# ConverterSch.net
KiCad netlist of a schematic drawn in Altium Designer
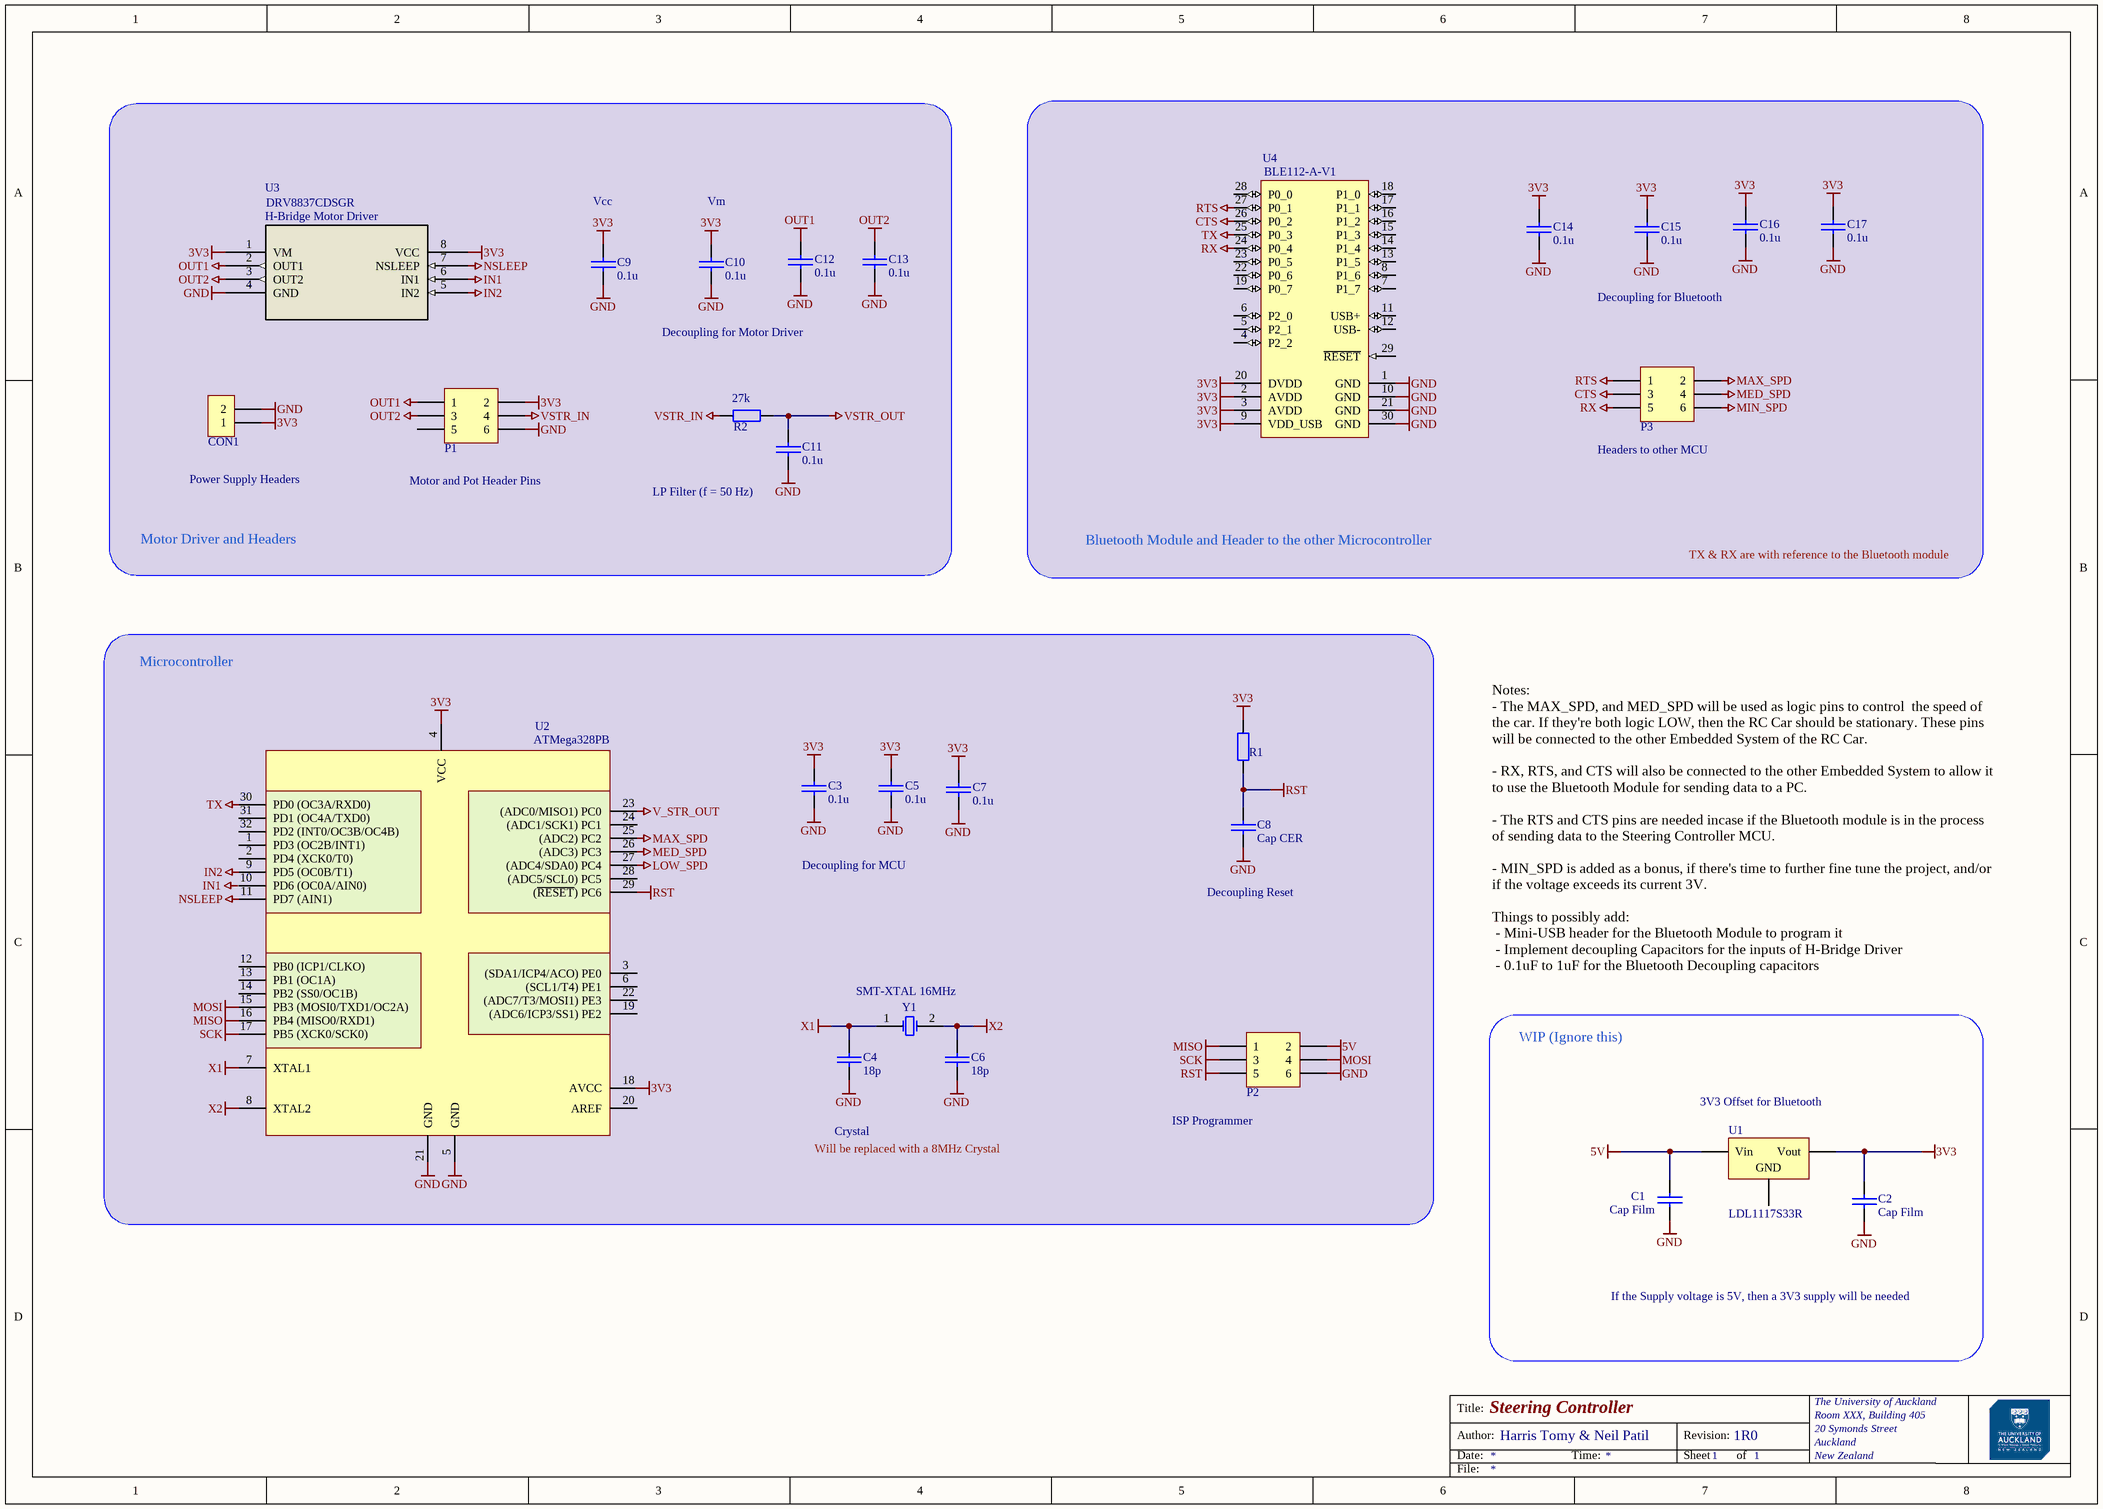
[diagram p0: ConverterSch.SchDoc]

(export (version "E")
  (design (tool "Eeschema 10.0.6"))
  (components
    (comp (ref "C1")
      (value "Cap Film")
      (footprint "LDECE4150KA0N00")
      (description "CAP FILM 1.5UF 10% 50VDC 2824")
      (fields (field (name "MPN") "LDECE4150KA0N00") (field (name "MANUFACTURER") "KEMET"))
      (libsource (lib "E209_Lib") (part "Cap Film SMD LDECE4150KA0N00"))
    )
    (comp (ref "C2")
      (value "Cap Film")
      (footprint "LDECE4150KA0N00")
      (description "CAP FILM 1.5UF 10% 50VDC 2824")
      (fields (field (name "MPN") "LDECE4150KA0N00") (field (name "MANUFACTURER") "KEMET"))
      (libsource (lib "E209_Lib") (part "Cap Film SMD LDECE4150KA0N00"))
    )
    (comp (ref "C3")
      (value "0.1u")
      (footprint "C1206")
      (description "CAP CER 0.1UF 100V C0G 1206")
      (fields (field (name "MPN") "C3216C0G2A104J160AC") (field (name "MANUFACTURER") "TDK Corporation"))
      (libsource (lib "E209_Lib") (part "Cap CER Decoup C3216C0G2A104J160AC"))
    )
    (comp (ref "C4")
      (value "18p")
      (footprint "C1206")
      (description "CAP CER 0.1UF 100V C0G 1206")
      (fields (field (name "MPN") "C3216C0G2A104J160AC") (field (name "MANUFACTURER") "TDK Corporation"))
      (libsource (lib "E209_Lib") (part "Cap CER Decoup C3216C0G2A104J160AC"))
    )
    (comp (ref "C5")
      (value "0.1u")
      (footprint "C1206")
      (description "CAP CER 0.1UF 100V C0G 1206")
      (fields (field (name "MPN") "C3216C0G2A104J160AC") (field (name "MANUFACTURER") "TDK Corporation"))
      (libsource (lib "E209_Lib") (part "Cap CER Decoup C3216C0G2A104J160AC"))
    )
    (comp (ref "C6")
      (value "18p")
      (footprint "C1206")
      (description "CAP CER 0.1UF 100V C0G 1206")
      (fields (field (name "MPN") "C3216C0G2A104J160AC") (field (name "MANUFACTURER") "TDK Corporation"))
      (libsource (lib "E209_Lib") (part "Cap CER Decoup C3216C0G2A104J160AC"))
    )
    (comp (ref "C7")
      (value "0.1u")
      (footprint "C1206")
      (description "CAP CER 0.1UF 100V C0G 1206")
      (fields (field (name "MPN") "C3216C0G2A104J160AC") (field (name "MANUFACTURER") "TDK Corporation"))
      (libsource (lib "E209_Lib") (part "Cap CER Decoup C3216C0G2A104J160AC"))
    )
    (comp (ref "C8")
      (value "Cap CER")
      (footprint "C1206")
      (description "CAP CER 0.1UF 100V C0G 1206")
      (fields (field (name "MPN") "C3216C0G2A104J160AC") (field (name "MANUFACTURER") "TDK Corporation"))
      (libsource (lib "E209_Lib") (part "Cap CER Decoup C3216C0G2A104J160AC"))
    )
    (comp (ref "C9")
      (value "0.1u")
      (footprint "C1206")
      (description "CAP CER 0.1UF 100V C0G 1206")
      (fields (field (name "MPN") "C3216C0G2A104J160AC") (field (name "MANUFACTURER") "TDK Corporation"))
      (libsource (lib "E209_Lib") (part "Cap CER Decoup C3216C0G2A104J160AC"))
    )
    (comp (ref "C10")
      (value "0.1u")
      (footprint "C1206")
      (description "CAP CER 0.1UF 100V C0G 1206")
      (fields (field (name "MPN") "C3216C0G2A104J160AC") (field (name "MANUFACTURER") "TDK Corporation"))
      (libsource (lib "E209_Lib") (part "Cap CER Decoup C3216C0G2A104J160AC"))
    )
    (comp (ref "C11")
      (value "0.1u")
      (footprint "C1206")
      (description "CAP CER 0.1UF 100V C0G 1206")
      (fields (field (name "MPN") "C3216C0G2A104J160AC") (field (name "MANUFACTURER") "TDK Corporation"))
      (libsource (lib "E209_Lib") (part "Cap CER Decoup C3216C0G2A104J160AC"))
    )
    (comp (ref "C12")
      (value "0.1u")
      (footprint "C1206")
      (description "CAP CER 0.1UF 100V C0G 1206")
      (fields (field (name "MPN") "C3216C0G2A104J160AC") (field (name "MANUFACTURER") "TDK Corporation"))
      (libsource (lib "E209_Lib") (part "Cap CER Decoup C3216C0G2A104J160AC"))
    )
    (comp (ref "C13")
      (value "0.1u")
      (footprint "C1206")
      (description "CAP CER 0.1UF 100V C0G 1206")
      (fields (field (name "MPN") "C3216C0G2A104J160AC") (field (name "MANUFACTURER") "TDK Corporation"))
      (libsource (lib "E209_Lib") (part "Cap CER Decoup C3216C0G2A104J160AC"))
    )
    (comp (ref "C14")
      (value "0.1u")
      (footprint "C1206")
      (description "CAP CER 0.1UF 100V C0G 1206")
      (fields (field (name "MPN") "C3216C0G2A104J160AC") (field (name "MANUFACTURER") "TDK Corporation"))
      (libsource (lib "E209_Lib") (part "Cap CER Decoup C3216C0G2A104J160AC"))
    )
    (comp (ref "C15")
      (value "0.1u")
      (footprint "C1206")
      (description "CAP CER 0.1UF 100V C0G 1206")
      (fields (field (name "MPN") "C3216C0G2A104J160AC") (field (name "MANUFACTURER") "TDK Corporation"))
      (libsource (lib "E209_Lib") (part "Cap CER Decoup C3216C0G2A104J160AC"))
    )
    (comp (ref "C16")
      (value "0.1u")
      (footprint "C1206")
      (description "CAP CER 0.1UF 100V C0G 1206")
      (fields (field (name "MPN") "C3216C0G2A104J160AC") (field (name "MANUFACTURER") "TDK Corporation"))
      (libsource (lib "E209_Lib") (part "Cap CER Decoup C3216C0G2A104J160AC"))
    )
    (comp (ref "C17")
      (value "0.1u")
      (footprint "C1206")
      (description "CAP CER 0.1UF 100V C0G 1206")
      (fields (field (name "MPN") "C3216C0G2A104J160AC") (field (name "MANUFACTURER") "TDK Corporation"))
      (libsource (lib "E209_Lib") (part "Cap CER Decoup C3216C0G2A104J160AC"))
    )
    (comp (ref "CON1")
      (value "Header 2X1")
      (footprint "HDR2X1_2P54")
      (libsource (lib "CommonDevices_V1") (part "HDR2X1"))
    )
    (comp (ref "P1")
      (value "HDR3X2")
      (footprint "HDR2X3_2P54")
      (description "Header, 3-Pin, Dual row")
      (libsource (lib "CommonDevices_V1") (part "HDR3X2"))
    )
    (comp (ref "P2")
      (value "HDR3X2")
      (footprint "HDR2X3_2P54")
      (description "Header, 3-Pin, Dual row")
      (libsource (lib "CommonDevices_V1") (part "HDR3X2"))
    )
    (comp (ref "P3")
      (value "HDR3X2")
      (footprint "HDR2X3_2P54")
      (description "Header, 3-Pin, Dual row")
      (libsource (lib "CommonDevices_V1") (part "HDR3X2"))
    )
    (comp (ref "R1")
      (value "Resistor 1206")
      (footprint "R1206")
      (description "RES1206")
      (fields (field (name "MPN") "?"))
      (libsource (lib "E209_Lib") (part "RES1206"))
    )
    (comp (ref "R2")
      (value "Resistor 0805")
      (footprint "R0805")
      (description "RES0805")
      (fields (field (name "MPN") "?"))
      (libsource (lib "E209_Lib") (part "RES0805"))
    )
    (comp (ref "U1")
      (value "LDL1117S33R")
      (footprint "SOT223L")
      (description "IC REG LINEAR 3.3V 1.2A SOT223")
      (fields (field (name "MANUFACTURER") "STMicroelectronics"))
      (libsource (lib "E209_Lib") (part "LDO LDL1117S33R"))
    )
    (comp (ref "U2")
      (value "ATMega328PB")
      (footprint "TQFP32")
      (description "IC MCU 8BIT 32KB FLASH 32TQFP")
      (libsource (lib "CommonDevices_V1") (part "ATMega328PB"))
    )
    (comp (ref "U3")
      (value "DRV8837CDSGR")
      (footprint "DSG8_P9X1P6_TEX")
      (description "No Description Available")
      (fields (field (name "COPYRIGHT") "Copyright (C) 2018 Accelerated Designs. All rights reserved"))
      (libsource (lib "H-Bridge_Driver_DRV8837C") (part "DRV8837CDSGR"))
    )
    (comp (ref "U4")
      (value "BLE112-A-V1")
      (footprint "BLUE-BLE112-A-V1_V")
      (libsource (lib "Integrated_Library1") (part "BLE112-A-V1"))
    )
    (comp (ref "Y1")
      (value "SMT-XTAL 16MHz")
      (footprint "HC49-US")
      (description "9C-16.000MAAJ-T crystal 16.0000MHZ 18PF SMD")
      (fields
        (field (name "MANUFACTURER") "TXC CORPORATION")
        (field (name "MANUFACTURER PART NUMBER") "9C-16.000MAAJ-T")
      )
      (libsource (lib "EE209_Library") (part "TXC9C-16_XTAL_SMT"))
    )
  )
  (nets
    (net (code "1") (name "3V3") (class "Default")
      (node (ref "C10") (pin "2") (pinfunction "2_2") (pintype "passive"))
      (node (ref "C14") (pin "2") (pinfunction "2_2") (pintype "passive"))
      (node (ref "C15") (pin "2") (pinfunction "2_2") (pintype "passive"))
      (node (ref "C16") (pin "2") (pinfunction "2_2") (pintype "passive"))
      (node (ref "C17") (pin "2") (pinfunction "2_2") (pintype "passive"))
      (node (ref "C2") (pin "2") (pinfunction "2_2") (pintype "passive"))
      (node (ref "C3") (pin "2") (pinfunction "2_2") (pintype "passive"))
      (node (ref "C5") (pin "2") (pinfunction "2_2") (pintype "passive"))
      (node (ref "C7") (pin "2") (pinfunction "2_2") (pintype "passive"))
      (node (ref "C9") (pin "2") (pinfunction "2_2") (pintype "passive"))
      (node (ref "CON1") (pin "1") (pinfunction "1_1") (pintype "passive"))
      (node (ref "P1") (pin "2") (pinfunction "2_2") (pintype "passive"))
      (node (ref "R1") (pin "1") (pinfunction "1_1") (pintype "passive"))
      (node (ref "U1") (pin "2") (pinfunction "Vout_2") (pintype "passive"))
      (node (ref "U2") (pin "4") (pinfunction "VCC_4") (pintype "passive"))
      (node (ref "U3") (pin "1") (pinfunction "VM_1") (pintype "power_in"))
      (node (ref "U3") (pin "8") (pinfunction "VCC_8") (pintype "power_in"))
      (node (ref "U4") (pin "2") (pinfunction "AVDD_2") (pintype "power_in"))
      (node (ref "U4") (pin "20") (pinfunction "DVDD_20") (pintype "power_in"))
      (node (ref "U4") (pin "3") (pinfunction "AVDD_3") (pintype "power_in"))
      (node (ref "U4") (pin "9") (pinfunction "VDD_USB_9") (pintype "power_in"))
    )
    (net (code "2") (name "5V") (class "Default")
      (node (ref "C1") (pin "2") (pinfunction "2_2") (pintype "passive"))
      (node (ref "P2") (pin "2") (pinfunction "2_2") (pintype "passive"))
      (node (ref "U1") (pin "3") (pinfunction "Vin_3") (pintype "passive"))
    )
    (net (code "3") (name "CTS") (class "Default")
      (node (ref "P3") (pin "3") (pinfunction "3_3") (pintype "passive"))
      (node (ref "U4") (pin "26") (pinfunction "P0_2_26") (pintype "bidirectional"))
    )
    (net (code "4") (name "GND") (class "Default")
      (node (ref "C1") (pin "1") (pinfunction "1_1") (pintype "passive"))
      (node (ref "C10") (pin "1") (pinfunction "1_1") (pintype "passive"))
      (node (ref "C11") (pin "1") (pinfunction "1_1") (pintype "passive"))
      (node (ref "C12") (pin "1") (pinfunction "1_1") (pintype "passive"))
      (node (ref "C13") (pin "1") (pinfunction "1_1") (pintype "passive"))
      (node (ref "C14") (pin "1") (pinfunction "1_1") (pintype "passive"))
      (node (ref "C15") (pin "1") (pinfunction "1_1") (pintype "passive"))
      (node (ref "C16") (pin "1") (pinfunction "1_1") (pintype "passive"))
      (node (ref "C17") (pin "1") (pinfunction "1_1") (pintype "passive"))
      (node (ref "C2") (pin "1") (pinfunction "1_1") (pintype "passive"))
      (node (ref "C3") (pin "1") (pinfunction "1_1") (pintype "passive"))
      (node (ref "C4") (pin "1") (pinfunction "1_1") (pintype "passive"))
      (node (ref "C5") (pin "1") (pinfunction "1_1") (pintype "passive"))
      (node (ref "C6") (pin "1") (pinfunction "1_1") (pintype "passive"))
      (node (ref "C7") (pin "1") (pinfunction "1_1") (pintype "passive"))
      (node (ref "C8") (pin "1") (pinfunction "1_1") (pintype "passive"))
      (node (ref "C9") (pin "1") (pinfunction "1_1") (pintype "passive"))
      (node (ref "CON1") (pin "2") (pinfunction "2_2") (pintype "passive"))
      (node (ref "P1") (pin "6") (pinfunction "6_6") (pintype "passive"))
      (node (ref "P2") (pin "6") (pinfunction "6_6") (pintype "passive"))
      (node (ref "U2") (pin "21") (pinfunction "GND_21") (pintype "passive"))
      (node (ref "U2") (pin "5") (pinfunction "GND_5") (pintype "passive"))
      (node (ref "U3") (pin "4") (pinfunction "GND_4") (pintype "power_in"))
      (node (ref "U4") (pin "1") (pinfunction "GND_1") (pintype "power_in"))
      (node (ref "U4") (pin "10") (pinfunction "GND_10") (pintype "power_in"))
      (node (ref "U4") (pin "21") (pinfunction "GND_21") (pintype "power_in"))
      (node (ref "U4") (pin "30") (pinfunction "GND_30") (pintype "power_in"))
    )
    (net (code "5") (name "IN1") (class "Default")
      (node (ref "U3") (pin "6") (pinfunction "IN1_6") (pintype "input"))
    )
    (net (code "6") (name "IN2") (class "Default")
      (node (ref "U2") (pin "9") (pinfunction "PD5_(OC0B/T1)_9") (pintype "passive"))
      (node (ref "U3") (pin "5") (pinfunction "IN2_5") (pintype "input"))
    )
    (net (code "7") (name "LOW_SPD") (class "Default")
      (node (ref "U2") (pin "27") (pinfunction "(ADC4/SDA0)_PC4_27") (pintype "passive"))
    )
    (net (code "8") (name "MAX_SPD") (class "Default")
      (node (ref "P3") (pin "2") (pinfunction "2_2") (pintype "passive"))
      (node (ref "U2") (pin "25") (pinfunction "(ADC2)_PC2_25") (pintype "passive"))
    )
    (net (code "9") (name "MED_SPD") (class "Default")
      (node (ref "P3") (pin "4") (pinfunction "4_4") (pintype "passive"))
      (node (ref "U2") (pin "26") (pinfunction "(ADC3)_PC3_26") (pintype "passive"))
    )
    (net (code "10") (name "MIN_SPD") (class "Default")
      (node (ref "P3") (pin "6") (pinfunction "6_6") (pintype "passive"))
    )
    (net (code "11") (name "MISO") (class "Default")
      (node (ref "P2") (pin "1") (pinfunction "1_1") (pintype "passive"))
      (node (ref "U2") (pin "16") (pinfunction "PB4_(MISO0/RXD1)_16") (pintype "passive"))
    )
    (net (code "12") (name "MOSI") (class "Default")
      (node (ref "P2") (pin "4") (pinfunction "4_4") (pintype "passive"))
      (node (ref "U2") (pin "15") (pinfunction "PB3_(MOSI0/TXD1/OC2A)_15") (pintype "passive"))
    )
    (net (code "13") (name "NSLEEP") (class "Default")
      (node (ref "U2") (pin "11") (pinfunction "PD7_(AIN1)_11") (pintype "passive"))
      (node (ref "U3") (pin "7") (pinfunction "NSLEEP_7") (pintype "input"))
    )
    (net (code "14") (name "OUT1") (class "Default")
      (node (ref "C12") (pin "2") (pinfunction "2_2") (pintype "passive"))
      (node (ref "P1") (pin "1") (pinfunction "1_1") (pintype "passive"))
      (node (ref "U3") (pin "2") (pinfunction "OUT1_2") (pintype "output"))
    )
    (net (code "15") (name "OUT2") (class "Default")
      (node (ref "C13") (pin "2") (pinfunction "2_2") (pintype "passive"))
      (node (ref "P1") (pin "3") (pinfunction "3_3") (pintype "passive"))
      (node (ref "U3") (pin "3") (pinfunction "OUT2_3") (pintype "output"))
    )
    (net (code "16") (name "RST") (class "Default")
      (node (ref "C8") (pin "2") (pinfunction "2_2") (pintype "passive"))
      (node (ref "P2") (pin "5") (pinfunction "5_5") (pintype "passive"))
      (node (ref "R1") (pin "2") (pinfunction "2_2") (pintype "passive"))
      (node (ref "U2") (pin "29") (pinfunction "(~{RESET})_PC6_29") (pintype "passive"))
    )
    (net (code "17") (name "RTS") (class "Default")
      (node (ref "P3") (pin "1") (pinfunction "1_1") (pintype "passive"))
      (node (ref "U4") (pin "27") (pinfunction "P0_1_27") (pintype "bidirectional"))
    )
    (net (code "18") (name "RX") (class "Default")
      (node (ref "P3") (pin "5") (pinfunction "5_5") (pintype "passive"))
      (node (ref "U4") (pin "24") (pinfunction "P0_4_24") (pintype "bidirectional"))
    )
    (net (code "19") (name "SCK") (class "Default")
      (node (ref "P2") (pin "3") (pinfunction "3_3") (pintype "passive"))
      (node (ref "U2") (pin "17") (pinfunction "PB5_(XCK0/SCK0)_17") (pintype "passive"))
    )
    (net (code "20") (name "TX") (class "Default")
      (node (ref "U2") (pin "30") (pinfunction "PD0_(OC3A/RXD0)_30") (pintype "passive"))
      (node (ref "U4") (pin "25") (pinfunction "P0_3_25") (pintype "bidirectional"))
    )
    (net (code "21") (name "VSTR_IN") (class "Default")
      (node (ref "P1") (pin "4") (pinfunction "4_4") (pintype "passive"))
      (node (ref "R2") (pin "1") (pinfunction "1_1") (pintype "passive"))
    )
    (net (code "22") (name "VSTR_OUT") (class "Default")
      (node (ref "C11") (pin "2") (pinfunction "2_2") (pintype "passive"))
      (node (ref "R2") (pin "2") (pinfunction "2_2") (pintype "passive"))
    )
    (net (code "23") (name "V_STR_OUT") (class "Default")
      (node (ref "U2") (pin "23") (pinfunction "(ADC0/MISO1)_PC0_23") (pintype "passive"))
    )
    (net (code "24") (name "X1") (class "Default")
      (node (ref "C4") (pin "2") (pinfunction "2_2") (pintype "passive"))
      (node (ref "U2") (pin "7") (pinfunction "XTAL1_7") (pintype "passive"))
      (node (ref "Y1") (pin "1") (pinfunction "OSC1_1") (pintype "passive"))
    )
    (net (code "25") (name "X2") (class "Default")
      (node (ref "C6") (pin "2") (pinfunction "2_2") (pintype "passive"))
      (node (ref "U2") (pin "8") (pinfunction "XTAL2_8") (pintype "passive"))
      (node (ref "Y1") (pin "2") (pinfunction "OSC2_2") (pintype "passive"))
    )
    (net (code "26") (name "unconnected-(P1-Pad5)") (class "Default")
      (node (ref "P1") (pin "5") (pinfunction "5_5") (pintype "passive"))
    )
    (net (code "27") (name "unconnected-(U1-GND-Pad1)") (class "Default")
      (node (ref "U1") (pin "1") (pinfunction "GND_1") (pintype "passive"))
    )
    (net (code "28") (name "unconnected-(U2-(ADC1{slash}SCK1)_PC1-Pad24)") (class "Default")
      (node (ref "U2") (pin "24") (pinfunction "(ADC1/SCK1)_PC1_24") (pintype "passive"))
    )
    (net (code "29") (name "unconnected-(U2-(ADC5{slash}SCL0)_PC5-Pad28)") (class "Default")
      (node (ref "U2") (pin "28") (pinfunction "(ADC5/SCL0)_PC5_28") (pintype "passive"))
    )
    (net (code "30") (name "unconnected-(U2-(ADC6{slash}ICP3{slash}SS1)_PE2-Pad19)") (class "Default")
      (node (ref "U2") (pin "19") (pinfunction "(ADC6/ICP3/SS1)_PE2_19") (pintype "passive"))
    )
    (net (code "31") (name "unconnected-(U2-(ADC7{slash}T3{slash}MOSI1)_PE3-Pad22)") (class "Default")
      (node (ref "U2") (pin "22") (pinfunction "(ADC7/T3/MOSI1)_PE3_22") (pintype "passive"))
    )
    (net (code "32") (name "unconnected-(U2-(SCL1{slash}T4)_PE1-Pad6)") (class "Default")
      (node (ref "U2") (pin "6") (pinfunction "(SCL1/T4)_PE1_6") (pintype "passive"))
    )
    (net (code "33") (name "unconnected-(U2-(SDA1{slash}ICP4{slash}ACO)_PE0-Pad3)") (class "Default")
      (node (ref "U2") (pin "3") (pinfunction "(SDA1/ICP4/ACO)_PE0_3") (pintype "passive"))
    )
    (net (code "34") (name "unconnected-(U2-AREF-Pad20)") (class "Default")
      (node (ref "U2") (pin "20") (pinfunction "AREF_20") (pintype "passive"))
    )
    (net (code "35") (name "unconnected-(U2-AVCC-Pad18)") (class "Default")
      (node (ref "U2") (pin "18") (pinfunction "AVCC_18") (pintype "passive"))
    )
    (net (code "36") (name "unconnected-(U2-PB0_(ICP1{slash}CLKO)-Pad12)") (class "Default")
      (node (ref "U2") (pin "12") (pinfunction "PB0_(ICP1/CLKO)_12") (pintype "passive"))
    )
    (net (code "37") (name "unconnected-(U2-PB1_(OC1A)-Pad13)") (class "Default")
      (node (ref "U2") (pin "13") (pinfunction "PB1_(OC1A)_13") (pintype "passive"))
    )
    (net (code "38") (name "unconnected-(U2-PB2_(SS0{slash}OC1B)-Pad14)") (class "Default")
      (node (ref "U2") (pin "14") (pinfunction "PB2_(SS0/OC1B)_14") (pintype "passive"))
    )
    (net (code "39") (name "unconnected-(U2-PD1_(OC4A{slash}TXD0)-Pad31)") (class "Default")
      (node (ref "U2") (pin "31") (pinfunction "PD1_(OC4A/TXD0)_31") (pintype "passive"))
    )
    (net (code "40") (name "unconnected-(U2-PD2_(INT0{slash}OC3B{slash}OC4B)-Pad32)") (class "Default")
      (node (ref "U2") (pin "32") (pinfunction "PD2_(INT0/OC3B/OC4B)_32") (pintype "passive"))
    )
    (net (code "41") (name "unconnected-(U2-PD3_(OC2B{slash}INT1)-Pad1)") (class "Default")
      (node (ref "U2") (pin "1") (pinfunction "PD3_(OC2B/INT1)_1") (pintype "passive"))
    )
    (net (code "42") (name "unconnected-(U2-PD4_(XCK0{slash}T0)-Pad2)") (class "Default")
      (node (ref "U2") (pin "2") (pinfunction "PD4_(XCK0/T0)_2") (pintype "passive"))
    )
    (net (code "43") (name "unconnected-(U2-PD6_(OC0A{slash}AIN0)-Pad10)") (class "Default")
      (node (ref "U2") (pin "10") (pinfunction "PD6_(OC0A/AIN0)_10") (pintype "passive"))
    )
    (net (code "44") (name "unconnected-(U4-P0_0-Pad28)") (class "Default")
      (node (ref "U4") (pin "28") (pinfunction "P0_0_28") (pintype "bidirectional"))
    )
    (net (code "45") (name "unconnected-(U4-P0_5-Pad23)") (class "Default")
      (node (ref "U4") (pin "23") (pinfunction "P0_5_23") (pintype "bidirectional"))
    )
    (net (code "46") (name "unconnected-(U4-P0_6-Pad22)") (class "Default")
      (node (ref "U4") (pin "22") (pinfunction "P0_6_22") (pintype "bidirectional"))
    )
    (net (code "47") (name "unconnected-(U4-P0_7-Pad19)") (class "Default")
      (node (ref "U4") (pin "19") (pinfunction "P0_7_19") (pintype "bidirectional"))
    )
    (net (code "48") (name "unconnected-(U4-P1_0-Pad18)") (class "Default")
      (node (ref "U4") (pin "18") (pinfunction "P1_0_18") (pintype "bidirectional"))
    )
    (net (code "49") (name "unconnected-(U4-P1_1-Pad17)") (class "Default")
      (node (ref "U4") (pin "17") (pinfunction "P1_1_17") (pintype "bidirectional"))
    )
    (net (code "50") (name "unconnected-(U4-P1_2-Pad16)") (class "Default")
      (node (ref "U4") (pin "16") (pinfunction "P1_2_16") (pintype "bidirectional"))
    )
    (net (code "51") (name "unconnected-(U4-P1_3-Pad15)") (class "Default")
      (node (ref "U4") (pin "15") (pinfunction "P1_3_15") (pintype "bidirectional"))
    )
    (net (code "52") (name "unconnected-(U4-P1_4-Pad14)") (class "Default")
      (node (ref "U4") (pin "14") (pinfunction "P1_4_14") (pintype "bidirectional"))
    )
    (net (code "53") (name "unconnected-(U4-P1_5-Pad13)") (class "Default")
      (node (ref "U4") (pin "13") (pinfunction "P1_5_13") (pintype "bidirectional"))
    )
    (net (code "54") (name "unconnected-(U4-P1_6-Pad8)") (class "Default")
      (node (ref "U4") (pin "8") (pinfunction "P1_6_8") (pintype "bidirectional"))
    )
    (net (code "55") (name "unconnected-(U4-P1_7-Pad7)") (class "Default")
      (node (ref "U4") (pin "7") (pinfunction "P1_7_7") (pintype "bidirectional"))
    )
    (net (code "56") (name "unconnected-(U4-P2_0-Pad6)") (class "Default")
      (node (ref "U4") (pin "6") (pinfunction "P2_0_6") (pintype "bidirectional"))
    )
    (net (code "57") (name "unconnected-(U4-P2_1-Pad5)") (class "Default")
      (node (ref "U4") (pin "5") (pinfunction "P2_1_5") (pintype "bidirectional"))
    )
    (net (code "58") (name "unconnected-(U4-P2_2-Pad4)") (class "Default")
      (node (ref "U4") (pin "4") (pinfunction "P2_2_4") (pintype "bidirectional"))
    )
    (net (code "59") (name "unconnected-(U4-USB+-Pad11)") (class "Default")
      (node (ref "U4") (pin "11") (pinfunction "USB+_11") (pintype "bidirectional"))
    )
    (net (code "60") (name "unconnected-(U4-USB--Pad12)") (class "Default")
      (node (ref "U4") (pin "12") (pinfunction "USB-_12") (pintype "bidirectional"))
    )
    (net (code "61") (name "unconnected-(U4-~{RESET}-Pad29)") (class "Default")
      (node (ref "U4") (pin "29") (pinfunction "~{RESET}_29") (pintype "input"))
    )
  )
)
